# Adapter_RepRap.net
KiCad netlist of a schematic drawn in EAGLE
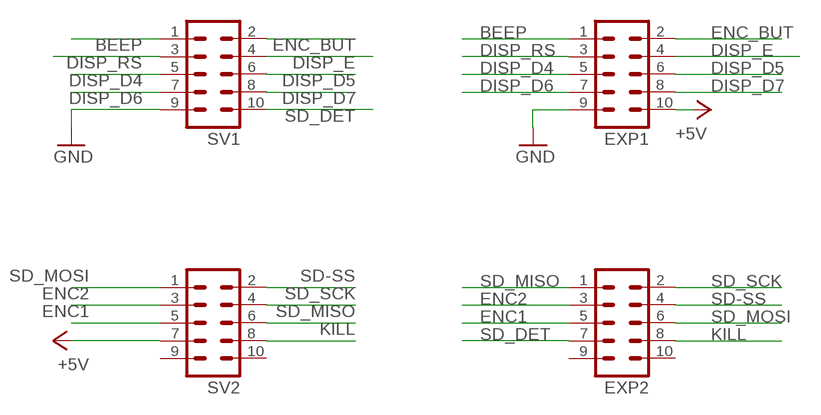
[diagram p0: schematic, sheet 1]

(export (version "E")
  (design (tool "Eeschema 10.0.6"))
  (components
    (comp (ref "EXP1")
      (value "ML10")
      (footprint "eagle-import:ML10")
      (libsource (lib "eagle-import") (part "ML10"))
    )
    (comp (ref "EXP2")
      (value "ML10")
      (footprint "eagle-import:ML10")
      (libsource (lib "eagle-import") (part "ML10"))
    )
    (comp (ref "SV1")
      (value "ML10")
      (footprint "eagle-import:ML10")
      (libsource (lib "eagle-import") (part "ML10"))
    )
    (comp (ref "SV2")
      (value "ML10")
      (footprint "eagle-import:ML10")
      (libsource (lib "eagle-import") (part "ML10"))
    )
  )
  (nets
    (net (code "1") (name "+5V") (class "Default")
      (node (ref "EXP1") (pin "10") (pinfunction "10_10") (pintype "passive"))
      (node (ref "SV2") (pin "7") (pinfunction "7_7") (pintype "passive"))
    )
    (net (code "2") (name "/BEEP") (class "Default")
      (node (ref "EXP1") (pin "1") (pinfunction "1_1") (pintype "passive"))
      (node (ref "SV1") (pin "1") (pinfunction "1_1") (pintype "passive"))
    )
    (net (code "3") (name "/DISP_D4") (class "Default")
      (node (ref "EXP1") (pin "5") (pinfunction "5_5") (pintype "passive"))
      (node (ref "SV1") (pin "5") (pinfunction "5_5") (pintype "passive"))
    )
    (net (code "4") (name "/DISP_D5") (class "Default")
      (node (ref "EXP1") (pin "6") (pinfunction "6_6") (pintype "passive"))
      (node (ref "SV1") (pin "6") (pinfunction "6_6") (pintype "passive"))
    )
    (net (code "5") (name "/DISP_D6") (class "Default")
      (node (ref "EXP1") (pin "7") (pinfunction "7_7") (pintype "passive"))
      (node (ref "SV1") (pin "7") (pinfunction "7_7") (pintype "passive"))
    )
    (net (code "6") (name "/DISP_D7") (class "Default")
      (node (ref "EXP1") (pin "8") (pinfunction "8_8") (pintype "passive"))
      (node (ref "SV1") (pin "8") (pinfunction "8_8") (pintype "passive"))
    )
    (net (code "7") (name "/DISP_E") (class "Default")
      (node (ref "EXP1") (pin "4") (pinfunction "4_4") (pintype "passive"))
      (node (ref "SV1") (pin "4") (pinfunction "4_4") (pintype "passive"))
    )
    (net (code "8") (name "/DISP_RS") (class "Default")
      (node (ref "EXP1") (pin "3") (pinfunction "3_3") (pintype "passive"))
      (node (ref "SV1") (pin "3") (pinfunction "3_3") (pintype "passive"))
    )
    (net (code "9") (name "/ENC1") (class "Default")
      (node (ref "EXP2") (pin "5") (pinfunction "5_5") (pintype "passive"))
      (node (ref "SV2") (pin "5") (pinfunction "5_5") (pintype "passive"))
    )
    (net (code "10") (name "/ENC2") (class "Default")
      (node (ref "EXP2") (pin "3") (pinfunction "3_3") (pintype "passive"))
      (node (ref "SV2") (pin "3") (pinfunction "3_3") (pintype "passive"))
    )
    (net (code "11") (name "/ENC_BUT") (class "Default")
      (node (ref "EXP1") (pin "2") (pinfunction "2_2") (pintype "passive"))
      (node (ref "SV1") (pin "2") (pinfunction "2_2") (pintype "passive"))
    )
    (net (code "12") (name "/KILL") (class "Default")
      (node (ref "EXP2") (pin "8") (pinfunction "8_8") (pintype "passive"))
      (node (ref "SV2") (pin "8") (pinfunction "8_8") (pintype "passive"))
    )
    (net (code "13") (name "/SD-SS") (class "Default")
      (node (ref "EXP2") (pin "4") (pinfunction "4_4") (pintype "passive"))
      (node (ref "SV2") (pin "2") (pinfunction "2_2") (pintype "passive"))
    )
    (net (code "14") (name "/SD_DET") (class "Default")
      (node (ref "EXP2") (pin "7") (pinfunction "7_7") (pintype "passive"))
      (node (ref "SV1") (pin "10") (pinfunction "10_10") (pintype "passive"))
    )
    (net (code "15") (name "/SD_MISO") (class "Default")
      (node (ref "EXP2") (pin "1") (pinfunction "1_1") (pintype "passive"))
      (node (ref "SV2") (pin "6") (pinfunction "6_6") (pintype "passive"))
    )
    (net (code "16") (name "/SD_MOSI") (class "Default")
      (node (ref "EXP2") (pin "6") (pinfunction "6_6") (pintype "passive"))
      (node (ref "SV2") (pin "1") (pinfunction "1_1") (pintype "passive"))
    )
    (net (code "17") (name "/SD_SCK") (class "Default")
      (node (ref "EXP2") (pin "2") (pinfunction "2_2") (pintype "passive"))
      (node (ref "SV2") (pin "4") (pinfunction "4_4") (pintype "passive"))
    )
    (net (code "18") (name "GND") (class "Default")
      (node (ref "EXP1") (pin "9") (pinfunction "9_9") (pintype "passive"))
      (node (ref "SV1") (pin "9") (pinfunction "9_9") (pintype "passive"))
    )
    (net (code "19") (name "unconnected-(EXP2-Pad9)") (class "Default")
      (node (ref "EXP2") (pin "9") (pinfunction "9_9") (pintype "passive"))
    )
    (net (code "20") (name "unconnected-(EXP2-Pad10)") (class "Default")
      (node (ref "EXP2") (pin "10") (pinfunction "10_10") (pintype "passive"))
    )
    (net (code "21") (name "unconnected-(SV2-Pad9)") (class "Default")
      (node (ref "SV2") (pin "9") (pinfunction "9_9") (pintype "passive"))
    )
    (net (code "22") (name "unconnected-(SV2-Pad10)") (class "Default")
      (node (ref "SV2") (pin "10") (pinfunction "10_10") (pintype "passive"))
    )
  )
)
